# Wall_Clock.net
KiCad netlist of a schematic drawn in Altium Designer
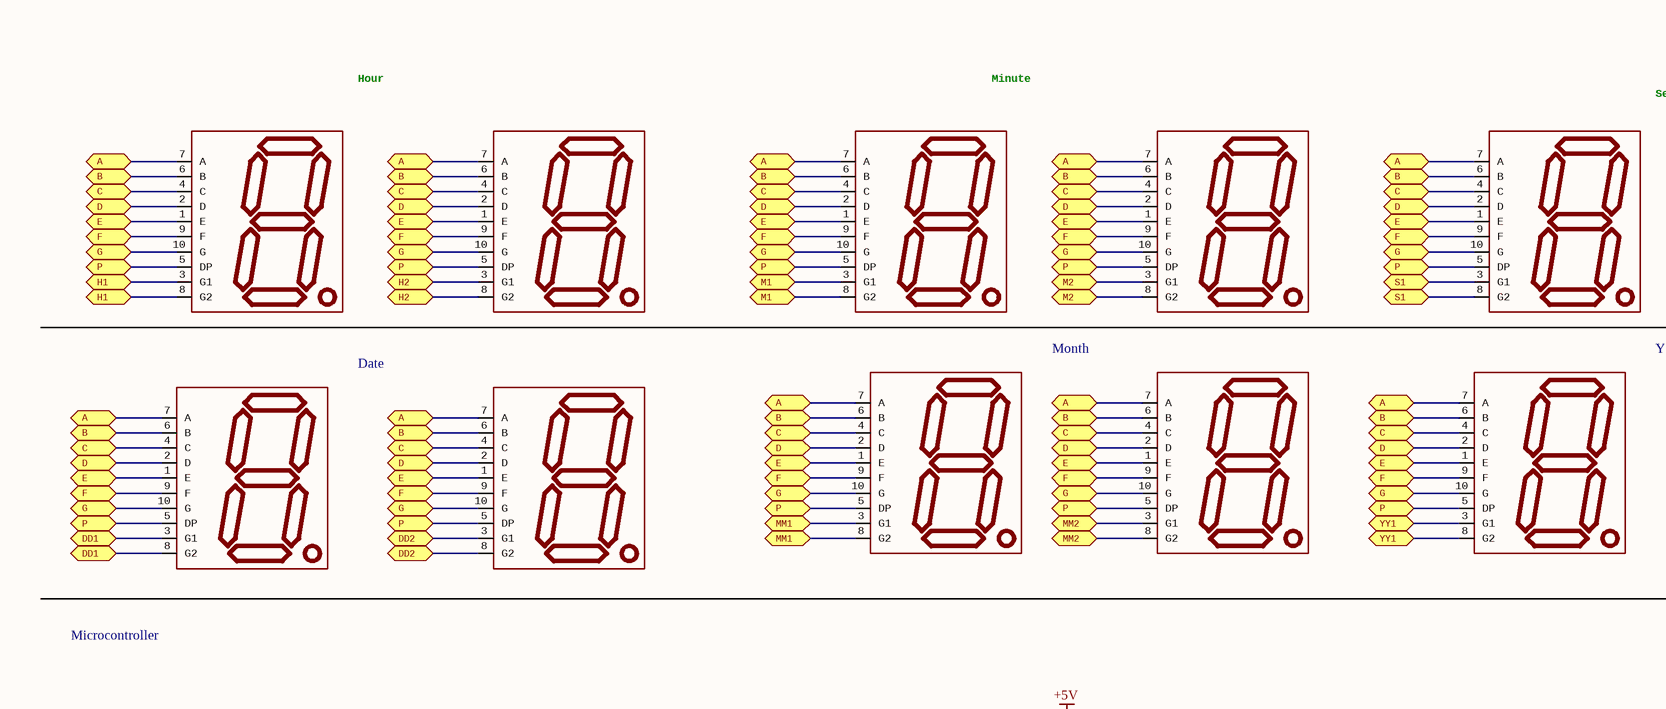
[diagram p0: Wall_Clock.SchDoc, top left]
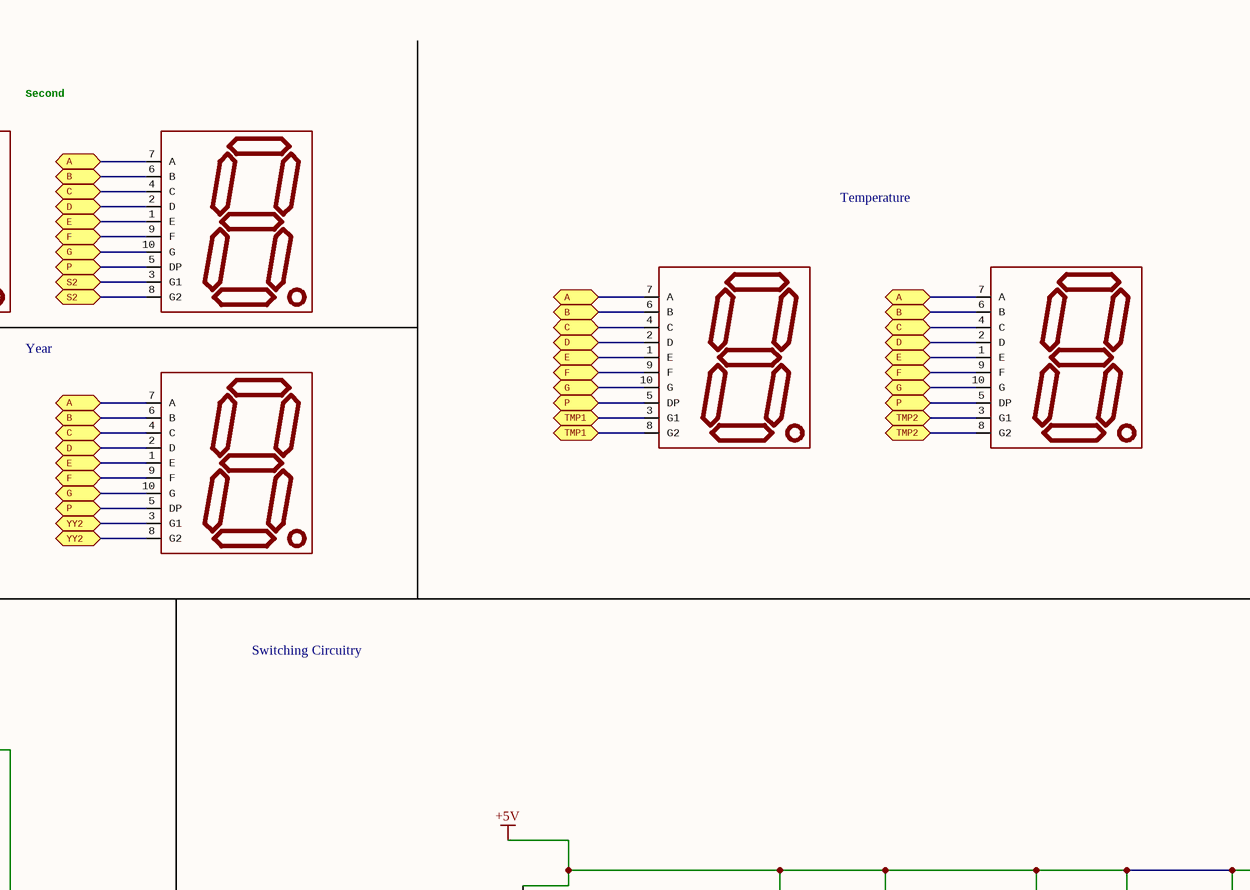
[diagram p1: Wall_Clock.SchDoc, top right]
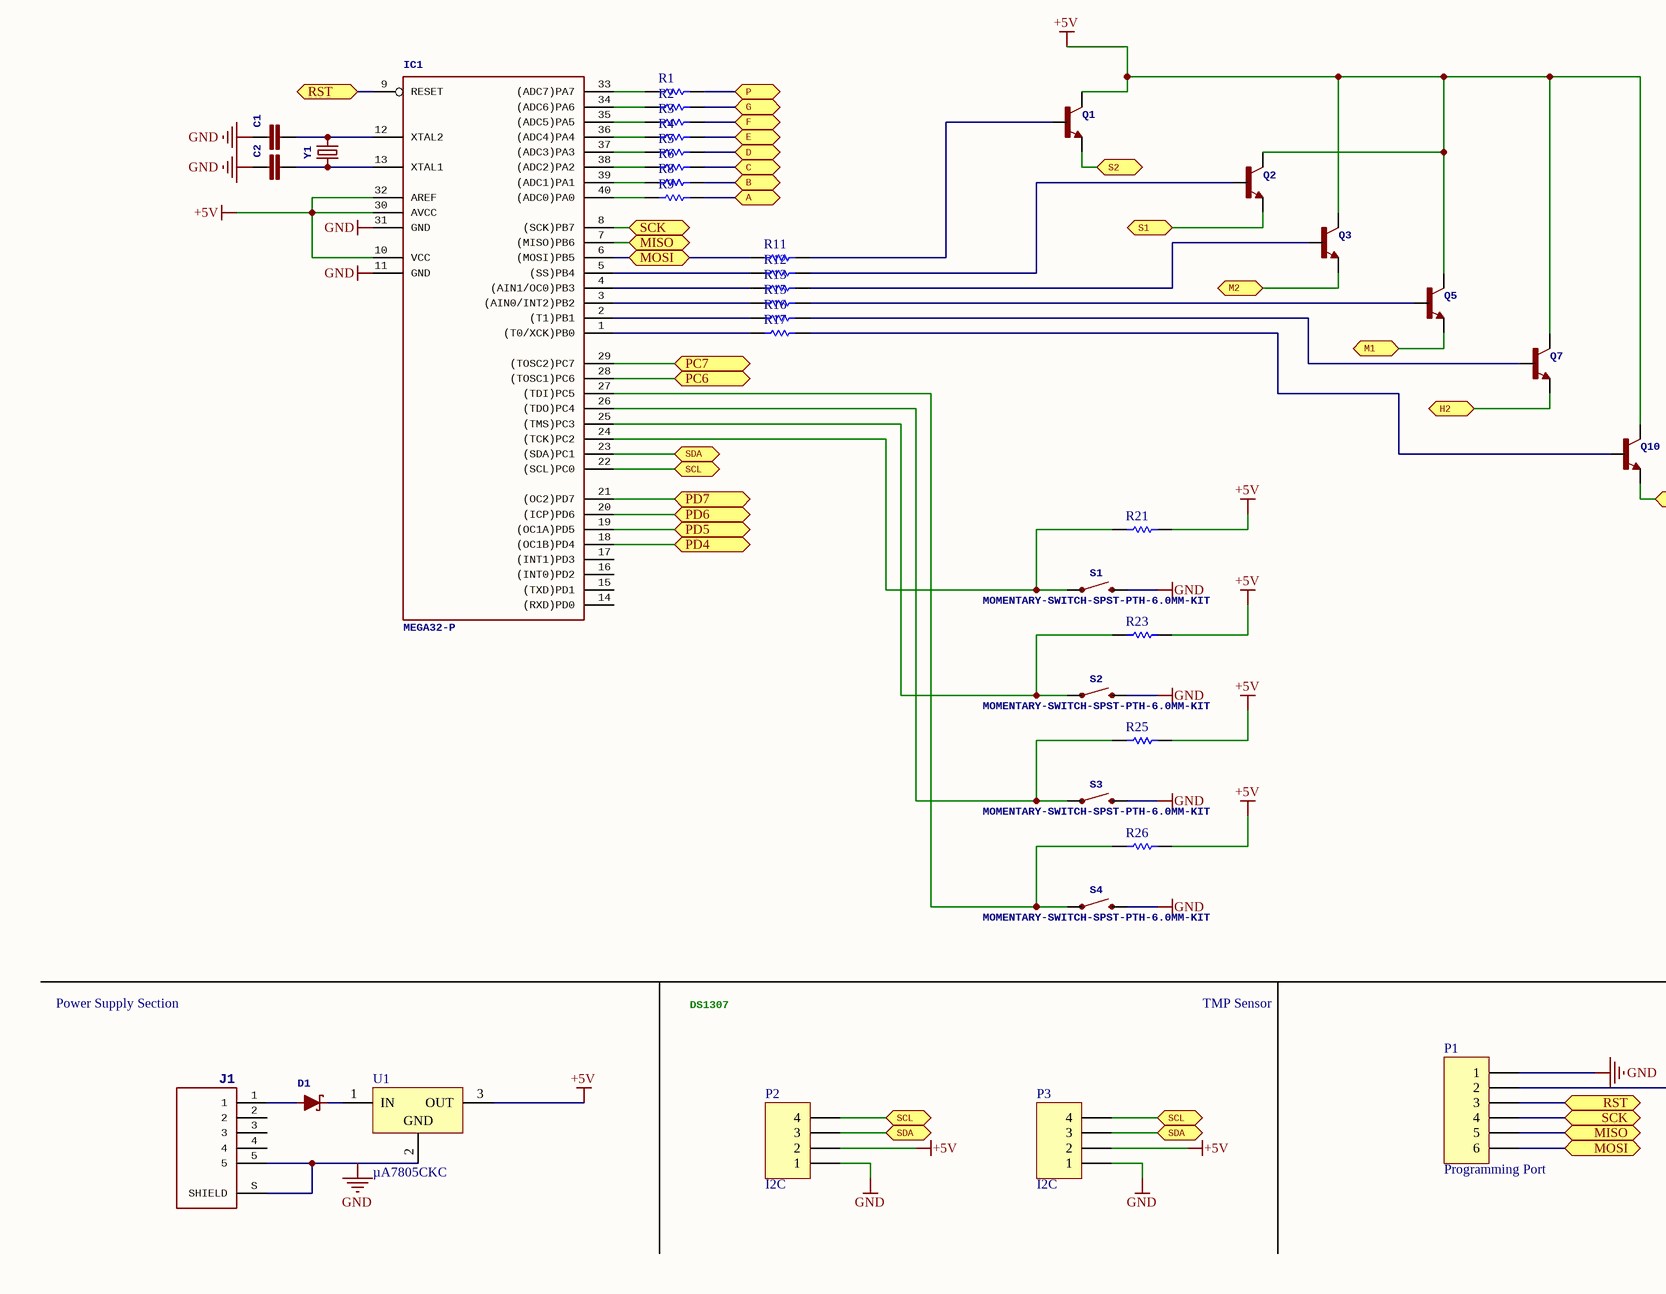
[diagram p2: Wall_Clock.SchDoc, bottom left]
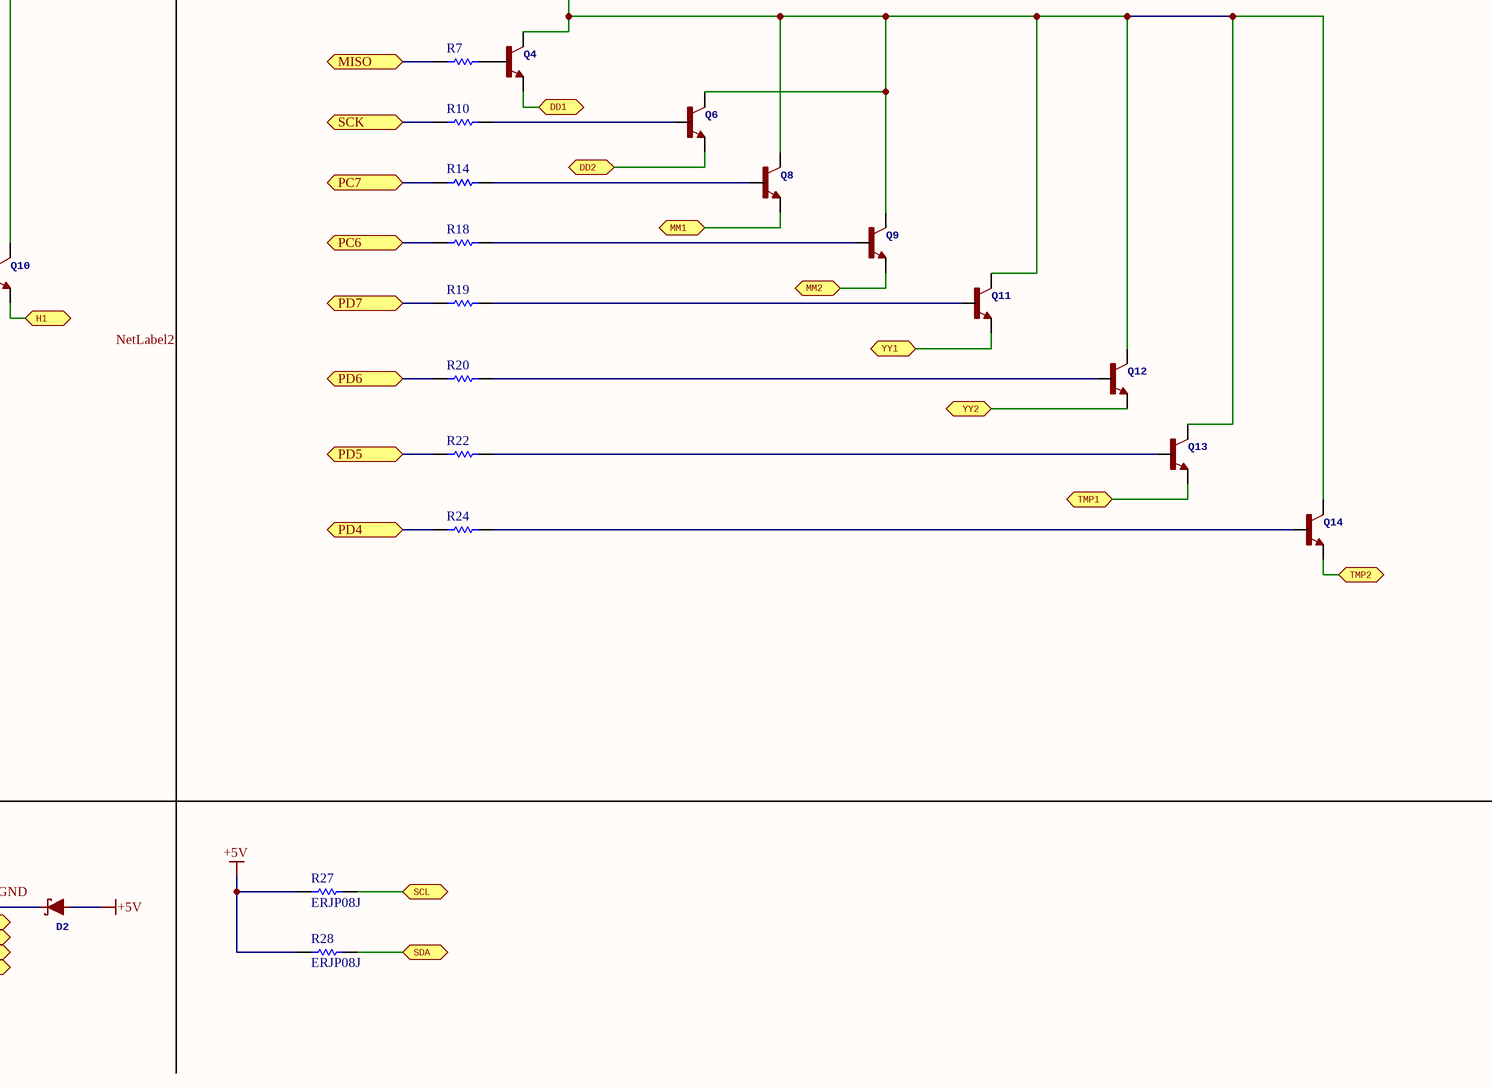
[diagram p3: Wall_Clock.SchDoc, bottom right]

(export (version "E")
  (design (tool "Eeschema 10.0.6"))
  (components
    (comp (ref "1")
      (value "7-SEGMENT-DISPLAYPTH")
      (footprint "7-SEGMENT-DISPLAY")
      (libsource (lib "SparkFun-Retired") (part "7-SEGMENT-DISPLAYPTH"))
    )
    (comp (ref "2")
      (value "7-SEGMENT-DISPLAYPTH")
      (footprint "7-SEGMENT-DISPLAY")
      (libsource (lib "SparkFun-Retired") (part "7-SEGMENT-DISPLAYPTH"))
    )
    (comp (ref "3")
      (value "7-SEGMENT-DISPLAYPTH")
      (footprint "7-SEGMENT-DISPLAY")
      (libsource (lib "SparkFun-Retired") (part "7-SEGMENT-DISPLAYPTH"))
    )
    (comp (ref "4")
      (value "7-SEGMENT-DISPLAYPTH")
      (footprint "7-SEGMENT-DISPLAY")
      (libsource (lib "SparkFun-Retired") (part "7-SEGMENT-DISPLAYPTH"))
    )
    (comp (ref "5")
      (value "7-SEGMENT-DISPLAYPTH")
      (footprint "7-SEGMENT-DISPLAY")
      (libsource (lib "SparkFun-Retired") (part "7-SEGMENT-DISPLAYPTH"))
    )
    (comp (ref "6")
      (value "7-SEGMENT-DISPLAYPTH")
      (footprint "7-SEGMENT-DISPLAY")
      (libsource (lib "SparkFun-Retired") (part "7-SEGMENT-DISPLAYPTH"))
    )
    (comp (ref "7")
      (value "7-SEGMENT-DISPLAYPTH")
      (footprint "7-SEGMENT-DISPLAY")
      (libsource (lib "SparkFun-Retired") (part "7-SEGMENT-DISPLAYPTH"))
    )
    (comp (ref "8")
      (value "7-SEGMENT-DISPLAYPTH")
      (footprint "7-SEGMENT-DISPLAY")
      (libsource (lib "SparkFun-Retired") (part "7-SEGMENT-DISPLAYPTH"))
    )
    (comp (ref "9")
      (value "7-SEGMENT-DISPLAYPTH")
      (footprint "7-SEGMENT-DISPLAY")
      (libsource (lib "SparkFun-Retired") (part "7-SEGMENT-DISPLAYPTH"))
    )
    (comp (ref "10")
      (value "7-SEGMENT-DISPLAYPTH")
      (footprint "7-SEGMENT-DISPLAY")
      (libsource (lib "SparkFun-Retired") (part "7-SEGMENT-DISPLAYPTH"))
    )
    (comp (ref "11")
      (value "7-SEGMENT-DISPLAYPTH")
      (footprint "7-SEGMENT-DISPLAY")
      (libsource (lib "SparkFun-Retired") (part "7-SEGMENT-DISPLAYPTH"))
    )
    (comp (ref "12")
      (value "7-SEGMENT-DISPLAYPTH")
      (footprint "7-SEGMENT-DISPLAY")
      (libsource (lib "SparkFun-Retired") (part "7-SEGMENT-DISPLAYPTH"))
    )
    (comp (ref "13")
      (value "7-SEGMENT-DISPLAYPTH")
      (footprint "7-SEGMENT-DISPLAY")
      (libsource (lib "SparkFun-Retired") (part "7-SEGMENT-DISPLAYPTH"))
    )
    (comp (ref "14")
      (value "7-SEGMENT-DISPLAYPTH")
      (footprint "7-SEGMENT-DISPLAY")
      (libsource (lib "SparkFun-Retired") (part "7-SEGMENT-DISPLAYPTH"))
    )
    (comp (ref "C1")
      (value "22PF-PTH-2.54MM-200V-5%")
      (footprint "CAP-PTH-2.54")
      (libsource (lib "SparkFun-Capacitors") (part "22PF-PTH-2.54MM-200V-5%"))
    )
    (comp (ref "C2")
      (value "22PF-PTH-2.54MM-200V-5%")
      (footprint "CAP-PTH-2.54")
      (libsource (lib "SparkFun-Capacitors") (part "22PF-PTH-2.54MM-200V-5%"))
    )
    (comp (ref "D1")
      (value "Schottky diode    A Schottky diode is a semiconductor diode which has a low forward voltage drop and a very fast switching action.")
      (footprint "SMA-DIODE")
      (libsource (lib "SparkFun-DiscreteSemi") (part "DIODE-SCHOTTKY-SS14"))
    )
    (comp (ref "D2")
      (value "Schottky diode    A Schottky diode is a semiconductor diode which has a low forward voltage drop and a very fast switching action.")
      (footprint "SMA-DIODE")
      (libsource (lib "SparkFun-DiscreteSemi") (part "DIODE-SCHOTTKY-SS14"))
    )
    (comp (ref "IC1")
      (value "MEGA32-P")
      (footprint "40P6")
      (fields (field (name "MPN") "ATMEGA32-16PU"))
      (libsource (lib "atmel") (part "MEGA32-P"))
    )
    (comp (ref "J1")
      (value "SMD+DIP Micro USB; MICRO-B-SMD")
      (footprint "HRS_ZX62D-B-5P8")
      (fields (field (name "MP") "ZX62D-B-5P8") (field (name "MF") "Hirose"))
      (libsource (lib "MicroUSB") (part "ZX62D-B-5P8"))
    )
    (comp (ref "P1")
      (value "Programming Port")
      (footprint "HDR1X6")
      (description "Header, 6-Pin")
      (fields (field (name "PUBLISHER") "Altium Limited"))
      (libsource (lib "Miscellaneous Connectors") (part "Header 6"))
    )
    (comp (ref "P2")
      (value "I2C")
      (footprint "HDR1X4")
      (description "Header, 4-Pin")
      (fields (field (name "PUBLISHER") "Altium Limited"))
      (libsource (lib "Miscellaneous Connectors") (part "Header 4"))
    )
    (comp (ref "P3")
      (value "I2C")
      (footprint "HDR1X4")
      (description "Header, 4-Pin")
      (fields (field (name "PUBLISHER") "Altium Limited"))
      (libsource (lib "Miscellaneous Connectors") (part "Header 4"))
    )
    (comp (ref "Q1")
      (value "NPN transistor    Current controlled devices typically used to amplify current or used as a switch.         BC547 -     COM-08928    (TO-92 45V 100mA) (1.Collector 2.Base 3.Emitter)             2N3904 -     COM-00521    (TO-92 40V 200mA) (1.Emitter 2.Base 3.Collector)             P2N2222A -     COM-12852    (TO-92 40V 600mA) (1.Collector 2.Base 3.Emitter)")
      (footprint "SOT23-3")
      (libsource (lib "SparkFun-DiscreteSemi") (part "TRANS_NPN-MMBT2222AL"))
    )
    (comp (ref "Q2")
      (value "NPN transistor    Current controlled devices typically used to amplify current or used as a switch.         BC547 -     COM-08928    (TO-92 45V 100mA) (1.Collector 2.Base 3.Emitter)             2N3904 -     COM-00521    (TO-92 40V 200mA) (1.Emitter 2.Base 3.Collector)             P2N2222A -     COM-12852    (TO-92 40V 600mA) (1.Collector 2.Base 3.Emitter)")
      (footprint "SOT23-3")
      (libsource (lib "SparkFun-DiscreteSemi") (part "TRANS_NPN-MMBT2222AL"))
    )
    (comp (ref "Q3")
      (value "NPN transistor    Current controlled devices typically used to amplify current or used as a switch.         BC547 -     COM-08928    (TO-92 45V 100mA) (1.Collector 2.Base 3.Emitter)             2N3904 -     COM-00521    (TO-92 40V 200mA) (1.Emitter 2.Base 3.Collector)             P2N2222A -     COM-12852    (TO-92 40V 600mA) (1.Collector 2.Base 3.Emitter)")
      (footprint "SOT23-3")
      (libsource (lib "SparkFun-DiscreteSemi") (part "TRANS_NPN-MMBT2222AL"))
    )
    (comp (ref "Q4")
      (value "NPN transistor    Current controlled devices typically used to amplify current or used as a switch.         BC547 -     COM-08928    (TO-92 45V 100mA) (1.Collector 2.Base 3.Emitter)             2N3904 -     COM-00521    (TO-92 40V 200mA) (1.Emitter 2.Base 3.Collector)             P2N2222A -     COM-12852    (TO-92 40V 600mA) (1.Collector 2.Base 3.Emitter)")
      (footprint "SOT23-3")
      (libsource (lib "SparkFun-DiscreteSemi") (part "TRANS_NPN-MMBT2222AL"))
    )
    (comp (ref "Q5")
      (value "NPN transistor    Current controlled devices typically used to amplify current or used as a switch.         BC547 -     COM-08928    (TO-92 45V 100mA) (1.Collector 2.Base 3.Emitter)             2N3904 -     COM-00521    (TO-92 40V 200mA) (1.Emitter 2.Base 3.Collector)             P2N2222A -     COM-12852    (TO-92 40V 600mA) (1.Collector 2.Base 3.Emitter)")
      (footprint "SOT23-3")
      (libsource (lib "SparkFun-DiscreteSemi") (part "TRANS_NPN-MMBT2222AL"))
    )
    (comp (ref "Q6")
      (value "NPN transistor    Current controlled devices typically used to amplify current or used as a switch.         BC547 -     COM-08928    (TO-92 45V 100mA) (1.Collector 2.Base 3.Emitter)             2N3904 -     COM-00521    (TO-92 40V 200mA) (1.Emitter 2.Base 3.Collector)             P2N2222A -     COM-12852    (TO-92 40V 600mA) (1.Collector 2.Base 3.Emitter)")
      (footprint "SOT23-3")
      (libsource (lib "SparkFun-DiscreteSemi") (part "TRANS_NPN-MMBT2222AL"))
    )
    (comp (ref "Q7")
      (value "NPN transistor    Current controlled devices typically used to amplify current or used as a switch.         BC547 -     COM-08928    (TO-92 45V 100mA) (1.Collector 2.Base 3.Emitter)             2N3904 -     COM-00521    (TO-92 40V 200mA) (1.Emitter 2.Base 3.Collector)             P2N2222A -     COM-12852    (TO-92 40V 600mA) (1.Collector 2.Base 3.Emitter)")
      (footprint "SOT23-3")
      (libsource (lib "SparkFun-DiscreteSemi") (part "TRANS_NPN-MMBT2222AL"))
    )
    (comp (ref "Q8")
      (value "NPN transistor    Current controlled devices typically used to amplify current or used as a switch.         BC547 -     COM-08928    (TO-92 45V 100mA) (1.Collector 2.Base 3.Emitter)             2N3904 -     COM-00521    (TO-92 40V 200mA) (1.Emitter 2.Base 3.Collector)             P2N2222A -     COM-12852    (TO-92 40V 600mA) (1.Collector 2.Base 3.Emitter)")
      (footprint "SOT23-3")
      (libsource (lib "SparkFun-DiscreteSemi") (part "TRANS_NPN-MMBT2222AL"))
    )
    (comp (ref "Q9")
      (value "NPN transistor    Current controlled devices typically used to amplify current or used as a switch.         BC547 -     COM-08928    (TO-92 45V 100mA) (1.Collector 2.Base 3.Emitter)             2N3904 -     COM-00521    (TO-92 40V 200mA) (1.Emitter 2.Base 3.Collector)             P2N2222A -     COM-12852    (TO-92 40V 600mA) (1.Collector 2.Base 3.Emitter)")
      (footprint "SOT23-3")
      (libsource (lib "SparkFun-DiscreteSemi") (part "TRANS_NPN-MMBT2222AL"))
    )
    (comp (ref "Q10")
      (value "NPN transistor    Current controlled devices typically used to amplify current or used as a switch.         BC547 -     COM-08928    (TO-92 45V 100mA) (1.Collector 2.Base 3.Emitter)             2N3904 -     COM-00521    (TO-92 40V 200mA) (1.Emitter 2.Base 3.Collector)             P2N2222A -     COM-12852    (TO-92 40V 600mA) (1.Collector 2.Base 3.Emitter)")
      (footprint "SOT23-3")
      (libsource (lib "SparkFun-DiscreteSemi") (part "TRANS_NPN-MMBT2222AL"))
    )
    (comp (ref "Q11")
      (value "NPN transistor    Current controlled devices typically used to amplify current or used as a switch.         BC547 -     COM-08928    (TO-92 45V 100mA) (1.Collector 2.Base 3.Emitter)             2N3904 -     COM-00521    (TO-92 40V 200mA) (1.Emitter 2.Base 3.Collector)             P2N2222A -     COM-12852    (TO-92 40V 600mA) (1.Collector 2.Base 3.Emitter)")
      (footprint "SOT23-3")
      (libsource (lib "SparkFun-DiscreteSemi") (part "TRANS_NPN-MMBT2222AL"))
    )
    (comp (ref "Q12")
      (value "NPN transistor    Current controlled devices typically used to amplify current or used as a switch.         BC547 -     COM-08928    (TO-92 45V 100mA) (1.Collector 2.Base 3.Emitter)             2N3904 -     COM-00521    (TO-92 40V 200mA) (1.Emitter 2.Base 3.Collector)             P2N2222A -     COM-12852    (TO-92 40V 600mA) (1.Collector 2.Base 3.Emitter)")
      (footprint "SOT23-3")
      (libsource (lib "SparkFun-DiscreteSemi") (part "TRANS_NPN-MMBT2222AL"))
    )
    (comp (ref "Q13")
      (value "NPN transistor    Current controlled devices typically used to amplify current or used as a switch.         BC547 -     COM-08928    (TO-92 45V 100mA) (1.Collector 2.Base 3.Emitter)             2N3904 -     COM-00521    (TO-92 40V 200mA) (1.Emitter 2.Base 3.Collector)             P2N2222A -     COM-12852    (TO-92 40V 600mA) (1.Collector 2.Base 3.Emitter)")
      (footprint "SOT23-3")
      (libsource (lib "SparkFun-DiscreteSemi") (part "TRANS_NPN-MMBT2222AL"))
    )
    (comp (ref "Q14")
      (value "NPN transistor    Current controlled devices typically used to amplify current or used as a switch.         BC547 -     COM-08928    (TO-92 45V 100mA) (1.Collector 2.Base 3.Emitter)             2N3904 -     COM-00521    (TO-92 40V 200mA) (1.Emitter 2.Base 3.Collector)             P2N2222A -     COM-12852    (TO-92 40V 600mA) (1.Collector 2.Base 3.Emitter)")
      (footprint "SOT23-3")
      (libsource (lib "SparkFun-DiscreteSemi") (part "TRANS_NPN-MMBT2222AL"))
    )
    (comp (ref "R1")
      (value "~")
      (footprint "8-1206")
      (description "Anti-Surge Thick Film Chip Resistor, 10 Ohm to 1M Ohm Range, 5% Tolerance, 1206 Size, 0.25 W")
      (fields (field (name "PUBLISHER") "Altium Limited"))
      (libsource (lib "Panasonic Resistor") (part "ERJP08J"))
    )
    (comp (ref "R2")
      (value "~")
      (footprint "8-1206")
      (description "Anti-Surge Thick Film Chip Resistor, 10 Ohm to 1M Ohm Range, 5% Tolerance, 1206 Size, 0.25 W")
      (fields (field (name "PUBLISHER") "Altium Limited"))
      (libsource (lib "Panasonic Resistor") (part "ERJP08J"))
    )
    (comp (ref "R3")
      (value "~")
      (footprint "8-1206")
      (description "Anti-Surge Thick Film Chip Resistor, 10 Ohm to 1M Ohm Range, 5% Tolerance, 1206 Size, 0.25 W")
      (fields (field (name "PUBLISHER") "Altium Limited"))
      (libsource (lib "Panasonic Resistor") (part "ERJP08J"))
    )
    (comp (ref "R4")
      (value "~")
      (footprint "8-1206")
      (description "Anti-Surge Thick Film Chip Resistor, 10 Ohm to 1M Ohm Range, 5% Tolerance, 1206 Size, 0.25 W")
      (fields (field (name "PUBLISHER") "Altium Limited"))
      (libsource (lib "Panasonic Resistor") (part "ERJP08J"))
    )
    (comp (ref "R5")
      (value "~")
      (footprint "8-1206")
      (description "Anti-Surge Thick Film Chip Resistor, 10 Ohm to 1M Ohm Range, 5% Tolerance, 1206 Size, 0.25 W")
      (fields (field (name "PUBLISHER") "Altium Limited"))
      (libsource (lib "Panasonic Resistor") (part "ERJP08J"))
    )
    (comp (ref "R6")
      (value "~")
      (footprint "8-1206")
      (description "Anti-Surge Thick Film Chip Resistor, 10 Ohm to 1M Ohm Range, 5% Tolerance, 1206 Size, 0.25 W")
      (fields (field (name "PUBLISHER") "Altium Limited"))
      (libsource (lib "Panasonic Resistor") (part "ERJP08J"))
    )
    (comp (ref "R7")
      (value "~")
      (footprint "8-1206")
      (description "Anti-Surge Thick Film Chip Resistor, 10 Ohm to 1M Ohm Range, 5% Tolerance, 1206 Size, 0.25 W")
      (fields (field (name "PUBLISHER") "Altium Limited"))
      (libsource (lib "Panasonic Resistor") (part "ERJP08J"))
    )
    (comp (ref "R8")
      (value "~")
      (footprint "8-1206")
      (description "Anti-Surge Thick Film Chip Resistor, 10 Ohm to 1M Ohm Range, 5% Tolerance, 1206 Size, 0.25 W")
      (fields (field (name "PUBLISHER") "Altium Limited"))
      (libsource (lib "Panasonic Resistor") (part "ERJP08J"))
    )
    (comp (ref "R9")
      (value "~")
      (footprint "8-1206")
      (description "Anti-Surge Thick Film Chip Resistor, 10 Ohm to 1M Ohm Range, 5% Tolerance, 1206 Size, 0.25 W")
      (fields (field (name "PUBLISHER") "Altium Limited"))
      (libsource (lib "Panasonic Resistor") (part "ERJP08J"))
    )
    (comp (ref "R10")
      (value "~")
      (footprint "8-1206")
      (description "Anti-Surge Thick Film Chip Resistor, 10 Ohm to 1M Ohm Range, 5% Tolerance, 1206 Size, 0.25 W")
      (fields (field (name "PUBLISHER") "Altium Limited"))
      (libsource (lib "Panasonic Resistor") (part "ERJP08J"))
    )
    (comp (ref "R11")
      (value "~")
      (footprint "8-1206")
      (description "Anti-Surge Thick Film Chip Resistor, 10 Ohm to 1M Ohm Range, 5% Tolerance, 1206 Size, 0.25 W")
      (fields (field (name "PUBLISHER") "Altium Limited"))
      (libsource (lib "Panasonic Resistor") (part "ERJP08J"))
    )
    (comp (ref "R12")
      (value "~")
      (footprint "8-1206")
      (description "Anti-Surge Thick Film Chip Resistor, 10 Ohm to 1M Ohm Range, 5% Tolerance, 1206 Size, 0.25 W")
      (fields (field (name "PUBLISHER") "Altium Limited"))
      (libsource (lib "Panasonic Resistor") (part "ERJP08J"))
    )
    (comp (ref "R13")
      (value "~")
      (footprint "8-1206")
      (description "Anti-Surge Thick Film Chip Resistor, 10 Ohm to 1M Ohm Range, 5% Tolerance, 1206 Size, 0.25 W")
      (fields (field (name "PUBLISHER") "Altium Limited"))
      (libsource (lib "Panasonic Resistor") (part "ERJP08J"))
    )
    (comp (ref "R14")
      (value "~")
      (footprint "8-1206")
      (description "Anti-Surge Thick Film Chip Resistor, 10 Ohm to 1M Ohm Range, 5% Tolerance, 1206 Size, 0.25 W")
      (fields (field (name "PUBLISHER") "Altium Limited"))
      (libsource (lib "Panasonic Resistor") (part "ERJP08J"))
    )
    (comp (ref "R15")
      (value "~")
      (footprint "8-1206")
      (description "Anti-Surge Thick Film Chip Resistor, 10 Ohm to 1M Ohm Range, 5% Tolerance, 1206 Size, 0.25 W")
      (fields (field (name "PUBLISHER") "Altium Limited"))
      (libsource (lib "Panasonic Resistor") (part "ERJP08J"))
    )
    (comp (ref "R16")
      (value "~")
      (footprint "8-1206")
      (description "Anti-Surge Thick Film Chip Resistor, 10 Ohm to 1M Ohm Range, 5% Tolerance, 1206 Size, 0.25 W")
      (fields (field (name "PUBLISHER") "Altium Limited"))
      (libsource (lib "Panasonic Resistor") (part "ERJP08J"))
    )
    (comp (ref "R17")
      (value "~")
      (footprint "8-1206")
      (description "Anti-Surge Thick Film Chip Resistor, 10 Ohm to 1M Ohm Range, 5% Tolerance, 1206 Size, 0.25 W")
      (fields (field (name "PUBLISHER") "Altium Limited"))
      (libsource (lib "Panasonic Resistor") (part "ERJP08J"))
    )
    (comp (ref "R18")
      (value "~")
      (footprint "8-1206")
      (description "Anti-Surge Thick Film Chip Resistor, 10 Ohm to 1M Ohm Range, 5% Tolerance, 1206 Size, 0.25 W")
      (fields (field (name "PUBLISHER") "Altium Limited"))
      (libsource (lib "Panasonic Resistor") (part "ERJP08J"))
    )
    (comp (ref "R19")
      (value "~")
      (footprint "8-1206")
      (description "Anti-Surge Thick Film Chip Resistor, 10 Ohm to 1M Ohm Range, 5% Tolerance, 1206 Size, 0.25 W")
      (fields (field (name "PUBLISHER") "Altium Limited"))
      (libsource (lib "Panasonic Resistor") (part "ERJP08J"))
    )
    (comp (ref "R20")
      (value "~")
      (footprint "8-1206")
      (description "Anti-Surge Thick Film Chip Resistor, 10 Ohm to 1M Ohm Range, 5% Tolerance, 1206 Size, 0.25 W")
      (fields (field (name "PUBLISHER") "Altium Limited"))
      (libsource (lib "Panasonic Resistor") (part "ERJP08J"))
    )
    (comp (ref "R21")
      (value "~")
      (footprint "8-1206")
      (description "Anti-Surge Thick Film Chip Resistor, 10 Ohm to 1M Ohm Range, 5% Tolerance, 1206 Size, 0.25 W")
      (fields (field (name "PUBLISHER") "Altium Limited"))
      (libsource (lib "Panasonic Resistor") (part "ERJP08J"))
    )
    (comp (ref "R22")
      (value "~")
      (footprint "8-1206")
      (description "Anti-Surge Thick Film Chip Resistor, 10 Ohm to 1M Ohm Range, 5% Tolerance, 1206 Size, 0.25 W")
      (fields (field (name "PUBLISHER") "Altium Limited"))
      (libsource (lib "Panasonic Resistor") (part "ERJP08J"))
    )
    (comp (ref "R23")
      (value "~")
      (footprint "8-1206")
      (description "Anti-Surge Thick Film Chip Resistor, 10 Ohm to 1M Ohm Range, 5% Tolerance, 1206 Size, 0.25 W")
      (fields (field (name "PUBLISHER") "Altium Limited"))
      (libsource (lib "Panasonic Resistor") (part "ERJP08J"))
    )
    (comp (ref "R24")
      (value "~")
      (footprint "8-1206")
      (description "Anti-Surge Thick Film Chip Resistor, 10 Ohm to 1M Ohm Range, 5% Tolerance, 1206 Size, 0.25 W")
      (fields (field (name "PUBLISHER") "Altium Limited"))
      (libsource (lib "Panasonic Resistor") (part "ERJP08J"))
    )
    (comp (ref "R25")
      (value "~")
      (footprint "8-1206")
      (description "Anti-Surge Thick Film Chip Resistor, 10 Ohm to 1M Ohm Range, 5% Tolerance, 1206 Size, 0.25 W")
      (fields (field (name "PUBLISHER") "Altium Limited"))
      (libsource (lib "Panasonic Resistor") (part "ERJP08J"))
    )
    (comp (ref "R26")
      (value "~")
      (footprint "8-1206")
      (description "Anti-Surge Thick Film Chip Resistor, 10 Ohm to 1M Ohm Range, 5% Tolerance, 1206 Size, 0.25 W")
      (fields (field (name "PUBLISHER") "Altium Limited"))
      (libsource (lib "Panasonic Resistor") (part "ERJP08J"))
    )
    (comp (ref "R27")
      (value "ERJP08J")
      (footprint "8-1206")
      (description "Anti-Surge Thick Film Chip Resistor, 10 Ohm to 1M Ohm Range, 5% Tolerance, 1206 Size, 0.25 W")
      (fields (field (name "PUBLISHER") "Altium Limited"))
      (libsource (lib "Panasonic Resistor") (part "ERJP08J"))
    )
    (comp (ref "R28")
      (value "ERJP08J")
      (footprint "8-1206")
      (description "Anti-Surge Thick Film Chip Resistor, 10 Ohm to 1M Ohm Range, 5% Tolerance, 1206 Size, 0.25 W")
      (fields (field (name "PUBLISHER") "Altium Limited"))
      (libsource (lib "Panasonic Resistor") (part "ERJP08J"))
    )
    (comp (ref "S1")
      (value "MOMENTARY-SWITCH-SPST-PTH-6.0MM-KIT")
      (footprint "TACTILE_SWITCH_PTH_6.0MM_KIT")
      (libsource (lib "SparkFun-Switches") (part "MOMENTARY-SWITCH-SPST-PTH-6.0MM-KIT"))
    )
    (comp (ref "S2")
      (value "MOMENTARY-SWITCH-SPST-PTH-6.0MM-KIT")
      (footprint "TACTILE_SWITCH_PTH_6.0MM_KIT")
      (libsource (lib "SparkFun-Switches") (part "MOMENTARY-SWITCH-SPST-PTH-6.0MM-KIT"))
    )
    (comp (ref "S3")
      (value "MOMENTARY-SWITCH-SPST-PTH-6.0MM-KIT")
      (footprint "TACTILE_SWITCH_PTH_6.0MM_KIT")
      (libsource (lib "SparkFun-Switches") (part "MOMENTARY-SWITCH-SPST-PTH-6.0MM-KIT"))
    )
    (comp (ref "S4")
      (value "MOMENTARY-SWITCH-SPST-PTH-6.0MM-KIT")
      (footprint "TACTILE_SWITCH_PTH_6.0MM_KIT")
      (libsource (lib "SparkFun-Switches") (part "MOMENTARY-SWITCH-SPST-PTH-6.0MM-KIT"))
    )
    (comp (ref "U1")
      (value "µA7805CKC")
      (footprint "KC03")
      (description "Positive-Voltage Regulator")
      (fields (field (name "PUBLISHER") "Altium Limited"))
      (libsource (lib "TI Power Mgt Voltage Regulator") (part "µA7805CKC"))
    )
    (comp (ref "Y1")
      (value "CRYSTAL-16MHZPTH-HC49US")
      (footprint "HC49US")
      (libsource (lib "SparkFun-Clocks") (part "CRYSTAL-16MHZPTH-HC49US"))
    )
  )
  (nets
    (net (code "1") (name "+5V") (class "Default")
      (node (ref "D2") (pin "A") (pinfunction "A_A") (pintype "passive"))
      (node (ref "IC1") (pin "10") (pinfunction "VCC_10") (pintype "power_in"))
      (node (ref "IC1") (pin "30") (pinfunction "AVCC_30") (pintype "power_in"))
      (node (ref "IC1") (pin "32") (pinfunction "AREF_32") (pintype "passive"))
      (node (ref "P2") (pin "2") (pinfunction "2_2") (pintype "passive"))
      (node (ref "P3") (pin "2") (pinfunction "2_2") (pintype "passive"))
      (node (ref "Q1") (pin "3") (pinfunction "C_3") (pintype "passive"))
      (node (ref "Q10") (pin "3") (pinfunction "C_3") (pintype "passive"))
      (node (ref "Q11") (pin "3") (pinfunction "C_3") (pintype "passive"))
      (node (ref "Q12") (pin "3") (pinfunction "C_3") (pintype "passive"))
      (node (ref "Q13") (pin "3") (pinfunction "C_3") (pintype "passive"))
      (node (ref "Q14") (pin "3") (pinfunction "C_3") (pintype "passive"))
      (node (ref "Q2") (pin "3") (pinfunction "C_3") (pintype "passive"))
      (node (ref "Q3") (pin "3") (pinfunction "C_3") (pintype "passive"))
      (node (ref "Q4") (pin "3") (pinfunction "C_3") (pintype "passive"))
      (node (ref "Q5") (pin "3") (pinfunction "C_3") (pintype "passive"))
      (node (ref "Q6") (pin "3") (pinfunction "C_3") (pintype "passive"))
      (node (ref "Q7") (pin "3") (pinfunction "C_3") (pintype "passive"))
      (node (ref "Q8") (pin "3") (pinfunction "C_3") (pintype "passive"))
      (node (ref "Q9") (pin "3") (pinfunction "C_3") (pintype "passive"))
      (node (ref "R21") (pin "2") (pinfunction "2_2") (pintype "passive"))
      (node (ref "R23") (pin "2") (pinfunction "2_2") (pintype "passive"))
      (node (ref "R25") (pin "2") (pinfunction "2_2") (pintype "passive"))
      (node (ref "R26") (pin "2") (pinfunction "2_2") (pintype "passive"))
      (node (ref "R27") (pin "1") (pinfunction "1_1") (pintype "passive"))
      (node (ref "R28") (pin "1") (pinfunction "1_1") (pintype "passive"))
      (node (ref "U1") (pin "3") (pinfunction "OUT_3") (pintype "power_in"))
    )
    (net (code "2") (name "/A") (class "Default")
      (node (ref "1") (pin "7") (pinfunction "A_7") (pintype "passive"))
      (node (ref "10") (pin "7") (pinfunction "A_7") (pintype "passive"))
      (node (ref "11") (pin "7") (pinfunction "A_7") (pintype "passive"))
      (node (ref "12") (pin "7") (pinfunction "A_7") (pintype "passive"))
      (node (ref "13") (pin "7") (pinfunction "A_7") (pintype "passive"))
      (node (ref "14") (pin "7") (pinfunction "A_7") (pintype "passive"))
      (node (ref "2") (pin "7") (pinfunction "A_7") (pintype "passive"))
      (node (ref "3") (pin "7") (pinfunction "A_7") (pintype "passive"))
      (node (ref "4") (pin "7") (pinfunction "A_7") (pintype "passive"))
      (node (ref "5") (pin "7") (pinfunction "A_7") (pintype "passive"))
      (node (ref "6") (pin "7") (pinfunction "A_7") (pintype "passive"))
      (node (ref "7") (pin "7") (pinfunction "A_7") (pintype "passive"))
      (node (ref "8") (pin "7") (pinfunction "A_7") (pintype "passive"))
      (node (ref "9") (pin "7") (pinfunction "A_7") (pintype "passive"))
      (node (ref "R9") (pin "2") (pinfunction "2_2") (pintype "passive"))
    )
    (net (code "3") (name "/B") (class "Default")
      (node (ref "1") (pin "6") (pinfunction "B_6") (pintype "passive"))
      (node (ref "10") (pin "6") (pinfunction "B_6") (pintype "passive"))
      (node (ref "11") (pin "6") (pinfunction "B_6") (pintype "passive"))
      (node (ref "12") (pin "6") (pinfunction "B_6") (pintype "passive"))
      (node (ref "13") (pin "6") (pinfunction "B_6") (pintype "passive"))
      (node (ref "14") (pin "6") (pinfunction "B_6") (pintype "passive"))
      (node (ref "2") (pin "6") (pinfunction "B_6") (pintype "passive"))
      (node (ref "3") (pin "6") (pinfunction "B_6") (pintype "passive"))
      (node (ref "4") (pin "6") (pinfunction "B_6") (pintype "passive"))
      (node (ref "5") (pin "6") (pinfunction "B_6") (pintype "passive"))
      (node (ref "6") (pin "6") (pinfunction "B_6") (pintype "passive"))
      (node (ref "7") (pin "6") (pinfunction "B_6") (pintype "passive"))
      (node (ref "8") (pin "6") (pinfunction "B_6") (pintype "passive"))
      (node (ref "9") (pin "6") (pinfunction "B_6") (pintype "passive"))
      (node (ref "R8") (pin "2") (pinfunction "2_2") (pintype "passive"))
    )
    (net (code "4") (name "/C") (class "Default")
      (node (ref "1") (pin "4") (pinfunction "C_4") (pintype "passive"))
      (node (ref "10") (pin "4") (pinfunction "C_4") (pintype "passive"))
      (node (ref "11") (pin "4") (pinfunction "C_4") (pintype "passive"))
      (node (ref "12") (pin "4") (pinfunction "C_4") (pintype "passive"))
      (node (ref "13") (pin "4") (pinfunction "C_4") (pintype "passive"))
      (node (ref "14") (pin "4") (pinfunction "C_4") (pintype "passive"))
      (node (ref "2") (pin "4") (pinfunction "C_4") (pintype "passive"))
      (node (ref "3") (pin "4") (pinfunction "C_4") (pintype "passive"))
      (node (ref "4") (pin "4") (pinfunction "C_4") (pintype "passive"))
      (node (ref "5") (pin "4") (pinfunction "C_4") (pintype "passive"))
      (node (ref "6") (pin "4") (pinfunction "C_4") (pintype "passive"))
      (node (ref "7") (pin "4") (pinfunction "C_4") (pintype "passive"))
      (node (ref "8") (pin "4") (pinfunction "C_4") (pintype "passive"))
      (node (ref "9") (pin "4") (pinfunction "C_4") (pintype "passive"))
      (node (ref "R6") (pin "2") (pinfunction "2_2") (pintype "passive"))
    )
    (net (code "5") (name "/D") (class "Default")
      (node (ref "1") (pin "2") (pinfunction "D_2") (pintype "passive"))
      (node (ref "10") (pin "2") (pinfunction "D_2") (pintype "passive"))
      (node (ref "11") (pin "2") (pinfunction "D_2") (pintype "passive"))
      (node (ref "12") (pin "2") (pinfunction "D_2") (pintype "passive"))
      (node (ref "13") (pin "2") (pinfunction "D_2") (pintype "passive"))
      (node (ref "14") (pin "2") (pinfunction "D_2") (pintype "passive"))
      (node (ref "2") (pin "2") (pinfunction "D_2") (pintype "passive"))
      (node (ref "3") (pin "2") (pinfunction "D_2") (pintype "passive"))
      (node (ref "4") (pin "2") (pinfunction "D_2") (pintype "passive"))
      (node (ref "5") (pin "2") (pinfunction "D_2") (pintype "passive"))
      (node (ref "6") (pin "2") (pinfunction "D_2") (pintype "passive"))
      (node (ref "7") (pin "2") (pinfunction "D_2") (pintype "passive"))
      (node (ref "8") (pin "2") (pinfunction "D_2") (pintype "passive"))
      (node (ref "9") (pin "2") (pinfunction "D_2") (pintype "passive"))
      (node (ref "R5") (pin "2") (pinfunction "2_2") (pintype "passive"))
    )
    (net (code "6") (name "/DD1") (class "Default")
      (node (ref "13") (pin "3") (pinfunction "G1_3") (pintype "passive"))
      (node (ref "13") (pin "8") (pinfunction "G2_8") (pintype "passive"))
      (node (ref "Q4") (pin "2") (pinfunction "E_2") (pintype "passive"))
    )
    (net (code "7") (name "/DD2") (class "Default")
      (node (ref "14") (pin "3") (pinfunction "G1_3") (pintype "passive"))
      (node (ref "14") (pin "8") (pinfunction "G2_8") (pintype "passive"))
      (node (ref "Q6") (pin "2") (pinfunction "E_2") (pintype "passive"))
    )
    (net (code "8") (name "/E") (class "Default")
      (node (ref "1") (pin "1") (pinfunction "E_1") (pintype "passive"))
      (node (ref "10") (pin "1") (pinfunction "E_1") (pintype "passive"))
      (node (ref "11") (pin "1") (pinfunction "E_1") (pintype "passive"))
      (node (ref "12") (pin "1") (pinfunction "E_1") (pintype "passive"))
      (node (ref "13") (pin "1") (pinfunction "E_1") (pintype "passive"))
      (node (ref "14") (pin "1") (pinfunction "E_1") (pintype "passive"))
      (node (ref "2") (pin "1") (pinfunction "E_1") (pintype "passive"))
      (node (ref "3") (pin "1") (pinfunction "E_1") (pintype "passive"))
      (node (ref "4") (pin "1") (pinfunction "E_1") (pintype "passive"))
      (node (ref "5") (pin "1") (pinfunction "E_1") (pintype "passive"))
      (node (ref "6") (pin "1") (pinfunction "E_1") (pintype "passive"))
      (node (ref "7") (pin "1") (pinfunction "E_1") (pintype "passive"))
      (node (ref "8") (pin "1") (pinfunction "E_1") (pintype "passive"))
      (node (ref "9") (pin "1") (pinfunction "E_1") (pintype "passive"))
      (node (ref "R4") (pin "2") (pinfunction "2_2") (pintype "passive"))
    )
    (net (code "9") (name "/F") (class "Default")
      (node (ref "1") (pin "9") (pinfunction "F_9") (pintype "passive"))
      (node (ref "10") (pin "9") (pinfunction "F_9") (pintype "passive"))
      (node (ref "11") (pin "9") (pinfunction "F_9") (pintype "passive"))
      (node (ref "12") (pin "9") (pinfunction "F_9") (pintype "passive"))
      (node (ref "13") (pin "9") (pinfunction "F_9") (pintype "passive"))
      (node (ref "14") (pin "9") (pinfunction "F_9") (pintype "passive"))
      (node (ref "2") (pin "9") (pinfunction "F_9") (pintype "passive"))
      (node (ref "3") (pin "9") (pinfunction "F_9") (pintype "passive"))
      (node (ref "4") (pin "9") (pinfunction "F_9") (pintype "passive"))
      (node (ref "5") (pin "9") (pinfunction "F_9") (pintype "passive"))
      (node (ref "6") (pin "9") (pinfunction "F_9") (pintype "passive"))
      (node (ref "7") (pin "9") (pinfunction "F_9") (pintype "passive"))
      (node (ref "8") (pin "9") (pinfunction "F_9") (pintype "passive"))
      (node (ref "9") (pin "9") (pinfunction "F_9") (pintype "passive"))
      (node (ref "R3") (pin "2") (pinfunction "2_2") (pintype "passive"))
    )
    (net (code "10") (name "/G") (class "Default")
      (node (ref "1") (pin "10") (pinfunction "G_10") (pintype "passive"))
      (node (ref "10") (pin "10") (pinfunction "G_10") (pintype "passive"))
      (node (ref "11") (pin "10") (pinfunction "G_10") (pintype "passive"))
      (node (ref "12") (pin "10") (pinfunction "G_10") (pintype "passive"))
      (node (ref "13") (pin "10") (pinfunction "G_10") (pintype "passive"))
      (node (ref "14") (pin "10") (pinfunction "G_10") (pintype "passive"))
      (node (ref "2") (pin "10") (pinfunction "G_10") (pintype "passive"))
      (node (ref "3") (pin "10") (pinfunction "G_10") (pintype "passive"))
      (node (ref "4") (pin "10") (pinfunction "G_10") (pintype "passive"))
      (node (ref "5") (pin "10") (pinfunction "G_10") (pintype "passive"))
      (node (ref "6") (pin "10") (pinfunction "G_10") (pintype "passive"))
      (node (ref "7") (pin "10") (pinfunction "G_10") (pintype "passive"))
      (node (ref "8") (pin "10") (pinfunction "G_10") (pintype "passive"))
      (node (ref "9") (pin "10") (pinfunction "G_10") (pintype "passive"))
      (node (ref "R2") (pin "2") (pinfunction "2_2") (pintype "passive"))
    )
    (net (code "11") (name "/H1") (class "Default")
      (node (ref "1") (pin "3") (pinfunction "G1_3") (pintype "passive"))
      (node (ref "1") (pin "8") (pinfunction "G2_8") (pintype "passive"))
      (node (ref "Q10") (pin "2") (pinfunction "E_2") (pintype "passive"))
    )
    (net (code "12") (name "/H2") (class "Default")
      (node (ref "2") (pin "3") (pinfunction "G1_3") (pintype "passive"))
      (node (ref "2") (pin "8") (pinfunction "G2_8") (pintype "passive"))
      (node (ref "Q7") (pin "2") (pinfunction "E_2") (pintype "passive"))
    )
    (net (code "13") (name "/M1") (class "Default")
      (node (ref "3") (pin "3") (pinfunction "G1_3") (pintype "passive"))
      (node (ref "3") (pin "8") (pinfunction "G2_8") (pintype "passive"))
      (node (ref "Q5") (pin "2") (pinfunction "E_2") (pintype "passive"))
    )
    (net (code "14") (name "/M2") (class "Default")
      (node (ref "4") (pin "3") (pinfunction "G1_3") (pintype "passive"))
      (node (ref "4") (pin "8") (pinfunction "G2_8") (pintype "passive"))
      (node (ref "Q3") (pin "2") (pinfunction "E_2") (pintype "passive"))
    )
    (net (code "15") (name "/MISO") (class "Default")
      (node (ref "IC1") (pin "7") (pinfunction "(MISO)PB6_7") (pintype "passive"))
      (node (ref "P1") (pin "5") (pinfunction "5_5") (pintype "passive"))
      (node (ref "R7") (pin "1") (pinfunction "1_1") (pintype "passive"))
    )
    (net (code "16") (name "/MM1") (class "Default")
      (node (ref "9") (pin "3") (pinfunction "G1_3") (pintype "passive"))
      (node (ref "9") (pin "8") (pinfunction "G2_8") (pintype "passive"))
      (node (ref "Q8") (pin "2") (pinfunction "E_2") (pintype "passive"))
    )
    (net (code "17") (name "/MM2") (class "Default")
      (node (ref "10") (pin "3") (pinfunction "G1_3") (pintype "passive"))
      (node (ref "10") (pin "8") (pinfunction "G2_8") (pintype "passive"))
      (node (ref "Q9") (pin "2") (pinfunction "E_2") (pintype "passive"))
    )
    (net (code "18") (name "/MOSI") (class "Default")
      (node (ref "IC1") (pin "6") (pinfunction "(MOSI)PB5_6") (pintype "passive"))
      (node (ref "P1") (pin "6") (pinfunction "6_6") (pintype "passive"))
      (node (ref "R11") (pin "1") (pinfunction "1_1") (pintype "passive"))
    )
    (net (code "20") (name "/P") (class "Default")
      (node (ref "1") (pin "5") (pinfunction "DP_5") (pintype "passive"))
      (node (ref "10") (pin "5") (pinfunction "DP_5") (pintype "passive"))
      (node (ref "11") (pin "5") (pinfunction "DP_5") (pintype "passive"))
      (node (ref "12") (pin "5") (pinfunction "DP_5") (pintype "passive"))
      (node (ref "13") (pin "5") (pinfunction "DP_5") (pintype "passive"))
      (node (ref "14") (pin "5") (pinfunction "DP_5") (pintype "passive"))
      (node (ref "2") (pin "5") (pinfunction "DP_5") (pintype "passive"))
      (node (ref "3") (pin "5") (pinfunction "DP_5") (pintype "passive"))
      (node (ref "4") (pin "5") (pinfunction "DP_5") (pintype "passive"))
      (node (ref "5") (pin "5") (pinfunction "DP_5") (pintype "passive"))
      (node (ref "6") (pin "5") (pinfunction "DP_5") (pintype "passive"))
      (node (ref "7") (pin "5") (pinfunction "DP_5") (pintype "passive"))
      (node (ref "8") (pin "5") (pinfunction "DP_5") (pintype "passive"))
      (node (ref "9") (pin "5") (pinfunction "DP_5") (pintype "passive"))
      (node (ref "R1") (pin "2") (pinfunction "2_2") (pintype "passive"))
    )
    (net (code "21") (name "/PC6") (class "Default")
      (node (ref "IC1") (pin "28") (pinfunction "(TOSC1)PC6_28") (pintype "passive"))
      (node (ref "R18") (pin "1") (pinfunction "1_1") (pintype "passive"))
    )
    (net (code "22") (name "/PC7") (class "Default")
      (node (ref "IC1") (pin "29") (pinfunction "(TOSC2)PC7_29") (pintype "passive"))
      (node (ref "R14") (pin "1") (pinfunction "1_1") (pintype "passive"))
    )
    (net (code "23") (name "/PD4") (class "Default")
      (node (ref "IC1") (pin "18") (pinfunction "(OC1B)PD4_18") (pintype "passive"))
      (node (ref "R24") (pin "1") (pinfunction "1_1") (pintype "passive"))
    )
    (net (code "24") (name "/PD5") (class "Default")
      (node (ref "IC1") (pin "19") (pinfunction "(OC1A)PD5_19") (pintype "passive"))
      (node (ref "R22") (pin "1") (pinfunction "1_1") (pintype "passive"))
    )
    (net (code "25") (name "/PD6") (class "Default")
      (node (ref "IC1") (pin "20") (pinfunction "(ICP)PD6_20") (pintype "passive"))
      (node (ref "R20") (pin "1") (pinfunction "1_1") (pintype "passive"))
    )
    (net (code "26") (name "/PD7") (class "Default")
      (node (ref "IC1") (pin "21") (pinfunction "(OC2)PD7_21") (pintype "passive"))
      (node (ref "R19") (pin "1") (pinfunction "1_1") (pintype "passive"))
    )
    (net (code "27") (name "/RST") (class "Default")
      (node (ref "IC1") (pin "9") (pinfunction "RESET_9") (pintype "passive"))
      (node (ref "P1") (pin "3") (pinfunction "3_3") (pintype "passive"))
    )
    (net (code "28") (name "/S1") (class "Default")
      (node (ref "5") (pin "3") (pinfunction "G1_3") (pintype "passive"))
      (node (ref "5") (pin "8") (pinfunction "G2_8") (pintype "passive"))
      (node (ref "Q2") (pin "2") (pinfunction "E_2") (pintype "passive"))
    )
    (net (code "29") (name "/S2") (class "Default")
      (node (ref "6") (pin "3") (pinfunction "G1_3") (pintype "passive"))
      (node (ref "6") (pin "8") (pinfunction "G2_8") (pintype "passive"))
      (node (ref "Q1") (pin "2") (pinfunction "E_2") (pintype "passive"))
    )
    (net (code "30") (name "/SCK") (class "Default")
      (node (ref "IC1") (pin "8") (pinfunction "(SCK)PB7_8") (pintype "passive"))
      (node (ref "P1") (pin "4") (pinfunction "4_4") (pintype "passive"))
      (node (ref "R10") (pin "1") (pinfunction "1_1") (pintype "passive"))
    )
    (net (code "31") (name "/SCL") (class "Default")
      (node (ref "IC1") (pin "22") (pinfunction "(SCL)PC0_22") (pintype "passive"))
      (node (ref "P2") (pin "4") (pinfunction "4_4") (pintype "passive"))
      (node (ref "P3") (pin "4") (pinfunction "4_4") (pintype "passive"))
      (node (ref "R27") (pin "2") (pinfunction "2_2") (pintype "passive"))
    )
    (net (code "32") (name "/SDA") (class "Default")
      (node (ref "IC1") (pin "23") (pinfunction "(SDA)PC1_23") (pintype "passive"))
      (node (ref "P2") (pin "3") (pinfunction "3_3") (pintype "passive"))
      (node (ref "P3") (pin "3") (pinfunction "3_3") (pintype "passive"))
      (node (ref "R28") (pin "2") (pinfunction "2_2") (pintype "passive"))
    )
    (net (code "33") (name "/TMP1") (class "Default")
      (node (ref "7") (pin "3") (pinfunction "G1_3") (pintype "passive"))
      (node (ref "7") (pin "8") (pinfunction "G2_8") (pintype "passive"))
      (node (ref "Q13") (pin "2") (pinfunction "E_2") (pintype "passive"))
    )
    (net (code "34") (name "/TMP2") (class "Default")
      (node (ref "8") (pin "3") (pinfunction "G1_3") (pintype "passive"))
      (node (ref "8") (pin "8") (pinfunction "G2_8") (pintype "passive"))
      (node (ref "Q14") (pin "2") (pinfunction "E_2") (pintype "passive"))
    )
    (net (code "35") (name "/YY1") (class "Default")
      (node (ref "11") (pin "3") (pinfunction "G1_3") (pintype "passive"))
      (node (ref "11") (pin "8") (pinfunction "G2_8") (pintype "passive"))
      (node (ref "Q11") (pin "2") (pinfunction "E_2") (pintype "passive"))
    )
    (net (code "36") (name "/YY2") (class "Default")
      (node (ref "12") (pin "3") (pinfunction "G1_3") (pintype "passive"))
      (node (ref "12") (pin "8") (pinfunction "G2_8") (pintype "passive"))
      (node (ref "Q12") (pin "2") (pinfunction "E_2") (pintype "passive"))
    )
    (net (code "37") (name "GND") (class "Default")
      (node (ref "C1") (pin "1") (pinfunction "1_1") (pintype "passive"))
      (node (ref "C2") (pin "1") (pinfunction "1_1") (pintype "passive"))
      (node (ref "IC1") (pin "11") (pinfunction "GND_11") (pintype "power_in"))
      (node (ref "IC1") (pin "31") (pinfunction "GND_31") (pintype "power_in"))
      (node (ref "J1") (pin "5") (pinfunction "5_5") (pintype "passive"))
      (node (ref "J1") (pin "S") (pinfunction "SHIELD_S") (pintype "passive"))
      (node (ref "P1") (pin "1") (pinfunction "1_1") (pintype "passive"))
      (node (ref "P2") (pin "1") (pinfunction "1_1") (pintype "passive"))
      (node (ref "P3") (pin "1") (pinfunction "1_1") (pintype "passive"))
      (node (ref "S1") (pin "3") (pinfunction "2_3") (pintype "passive"))
      (node (ref "S2") (pin "3") (pinfunction "2_3") (pintype "passive"))
      (node (ref "S3") (pin "3") (pinfunction "2_3") (pintype "passive"))
      (node (ref "S4") (pin "3") (pinfunction "2_3") (pintype "passive"))
      (node (ref "U1") (pin "2") (pinfunction "GND_2") (pintype "power_in"))
    )
    (net (code "38") (name "Net-(D1-PadA)") (class "Default")
      (node (ref "D1") (pin "A") (pinfunction "A_A") (pintype "passive"))
      (node (ref "J1") (pin "1") (pinfunction "1_1") (pintype "passive"))
    )
    (net (code "39") (name "Net-(D2-PadC)") (class "Default")
      (node (ref "D2") (pin "C") (pinfunction "C_C") (pintype "passive"))
      (node (ref "P1") (pin "2") (pinfunction "2_2") (pintype "passive"))
    )
    (net (code "40") (name "Net-(IC1-(ADC0)PA0)") (class "Default")
      (node (ref "IC1") (pin "40") (pinfunction "(ADC0)PA0_40") (pintype "passive"))
      (node (ref "R9") (pin "1") (pinfunction "1_1") (pintype "passive"))
    )
    (net (code "41") (name "Net-(IC1-(ADC1)PA1)") (class "Default")
      (node (ref "IC1") (pin "39") (pinfunction "(ADC1)PA1_39") (pintype "passive"))
      (node (ref "R8") (pin "1") (pinfunction "1_1") (pintype "passive"))
    )
    (net (code "42") (name "Net-(IC1-(ADC2)PA2)") (class "Default")
      (node (ref "IC1") (pin "38") (pinfunction "(ADC2)PA2_38") (pintype "passive"))
      (node (ref "R6") (pin "1") (pinfunction "1_1") (pintype "passive"))
    )
    (net (code "43") (name "Net-(IC1-(ADC3)PA3)") (class "Default")
      (node (ref "IC1") (pin "37") (pinfunction "(ADC3)PA3_37") (pintype "passive"))
      (node (ref "R5") (pin "1") (pinfunction "1_1") (pintype "passive"))
    )
    (net (code "44") (name "Net-(IC1-(ADC4)PA4)") (class "Default")
      (node (ref "IC1") (pin "36") (pinfunction "(ADC4)PA4_36") (pintype "passive"))
      (node (ref "R4") (pin "1") (pinfunction "1_1") (pintype "passive"))
    )
    (net (code "45") (name "Net-(IC1-(ADC5)PA5)") (class "Default")
      (node (ref "IC1") (pin "35") (pinfunction "(ADC5)PA5_35") (pintype "passive"))
      (node (ref "R3") (pin "1") (pinfunction "1_1") (pintype "passive"))
    )
    (net (code "46") (name "Net-(IC1-(ADC6)PA6)") (class "Default")
      (node (ref "IC1") (pin "34") (pinfunction "(ADC6)PA6_34") (pintype "passive"))
      (node (ref "R2") (pin "1") (pinfunction "1_1") (pintype "passive"))
    )
    (net (code "47") (name "Net-(IC1-(ADC7)PA7)") (class "Default")
      (node (ref "IC1") (pin "33") (pinfunction "(ADC7)PA7_33") (pintype "passive"))
      (node (ref "R1") (pin "1") (pinfunction "1_1") (pintype "passive"))
    )
    (net (code "48") (name "Net-(IC1-(AIN0{slash}INT2)PB2)") (class "Default")
      (node (ref "IC1") (pin "3") (pinfunction "(AIN0/INT2)PB2_3") (pintype "passive"))
      (node (ref "R15") (pin "1") (pinfunction "1_1") (pintype "passive"))
    )
    (net (code "49") (name "Net-(IC1-(AIN1{slash}OC0)PB3)") (class "Default")
      (node (ref "IC1") (pin "4") (pinfunction "(AIN1/OC0)PB3_4") (pintype "passive"))
      (node (ref "R13") (pin "1") (pinfunction "1_1") (pintype "passive"))
    )
    (net (code "50") (name "Net-(IC1-(SS)PB4)") (class "Default")
      (node (ref "IC1") (pin "5") (pinfunction "(SS)PB4_5") (pintype "passive"))
      (node (ref "R12") (pin "1") (pinfunction "1_1") (pintype "passive"))
    )
    (net (code "51") (name "Net-(IC1-(T0{slash}XCK)PB0)") (class "Default")
      (node (ref "IC1") (pin "1") (pinfunction "(T0/XCK)PB0_1") (pintype "passive"))
      (node (ref "R17") (pin "1") (pinfunction "1_1") (pintype "passive"))
    )
    (net (code "52") (name "Net-(IC1-(T1)PB1)") (class "Default")
      (node (ref "IC1") (pin "2") (pinfunction "(T1)PB1_2") (pintype "passive"))
      (node (ref "R16") (pin "1") (pinfunction "1_1") (pintype "passive"))
    )
    (net (code "53") (name "Net-(IC1-(TCK)PC2)") (class "Default")
      (node (ref "IC1") (pin "24") (pinfunction "(TCK)PC2_24") (pintype "passive"))
      (node (ref "R21") (pin "1") (pinfunction "1_1") (pintype "passive"))
      (node (ref "S1") (pin "1") (pinfunction "1_1") (pintype "passive"))
    )
    (net (code "54") (name "Net-(IC1-(TDI)PC5)") (class "Default")
      (node (ref "IC1") (pin "27") (pinfunction "(TDI)PC5_27") (pintype "passive"))
      (node (ref "R26") (pin "1") (pinfunction "1_1") (pintype "passive"))
      (node (ref "S4") (pin "1") (pinfunction "1_1") (pintype "passive"))
    )
    (net (code "55") (name "Net-(IC1-(TDO)PC4)") (class "Default")
      (node (ref "IC1") (pin "26") (pinfunction "(TDO)PC4_26") (pintype "passive"))
      (node (ref "R25") (pin "1") (pinfunction "1_1") (pintype "passive"))
      (node (ref "S3") (pin "1") (pinfunction "1_1") (pintype "passive"))
    )
    (net (code "56") (name "Net-(IC1-(TMS)PC3)") (class "Default")
      (node (ref "IC1") (pin "25") (pinfunction "(TMS)PC3_25") (pintype "passive"))
      (node (ref "R23") (pin "1") (pinfunction "1_1") (pintype "passive"))
      (node (ref "S2") (pin "1") (pinfunction "1_1") (pintype "passive"))
    )
    (net (code "57") (name "Net-(IC1-XTAL1)") (class "Default")
      (node (ref "C2") (pin "2") (pinfunction "2_2") (pintype "passive"))
      (node (ref "IC1") (pin "13") (pinfunction "XTAL1_13") (pintype "passive"))
      (node (ref "Y1") (pin "1") (pinfunction "1_1") (pintype "passive"))
    )
    (net (code "58") (name "Net-(IC1-XTAL2)") (class "Default")
      (node (ref "C1") (pin "2") (pinfunction "2_2") (pintype "passive"))
      (node (ref "IC1") (pin "12") (pinfunction "XTAL2_12") (pintype "passive"))
      (node (ref "Y1") (pin "2") (pinfunction "2_2") (pintype "passive"))
    )
    (net (code "59") (name "Net-(Q1-B)") (class "Default")
      (node (ref "Q1") (pin "1") (pinfunction "B_1") (pintype "passive"))
      (node (ref "R11") (pin "2") (pinfunction "2_2") (pintype "passive"))
    )
    (net (code "60") (name "Net-(Q2-B)") (class "Default")
      (node (ref "Q2") (pin "1") (pinfunction "B_1") (pintype "passive"))
      (node (ref "R12") (pin "2") (pinfunction "2_2") (pintype "passive"))
    )
    (net (code "61") (name "Net-(Q3-B)") (class "Default")
      (node (ref "Q3") (pin "1") (pinfunction "B_1") (pintype "passive"))
      (node (ref "R13") (pin "2") (pinfunction "2_2") (pintype "passive"))
    )
    (net (code "62") (name "Net-(Q4-B)") (class "Default")
      (node (ref "Q4") (pin "1") (pinfunction "B_1") (pintype "passive"))
      (node (ref "R7") (pin "2") (pinfunction "2_2") (pintype "passive"))
    )
    (net (code "63") (name "Net-(Q5-B)") (class "Default")
      (node (ref "Q5") (pin "1") (pinfunction "B_1") (pintype "passive"))
      (node (ref "R15") (pin "2") (pinfunction "2_2") (pintype "passive"))
    )
    (net (code "64") (name "Net-(Q6-B)") (class "Default")
      (node (ref "Q6") (pin "1") (pinfunction "B_1") (pintype "passive"))
      (node (ref "R10") (pin "2") (pinfunction "2_2") (pintype "passive"))
    )
    (net (code "65") (name "Net-(Q7-B)") (class "Default")
      (node (ref "Q7") (pin "1") (pinfunction "B_1") (pintype "passive"))
      (node (ref "R16") (pin "2") (pinfunction "2_2") (pintype "passive"))
    )
    (net (code "66") (name "Net-(Q8-B)") (class "Default")
      (node (ref "Q8") (pin "1") (pinfunction "B_1") (pintype "passive"))
      (node (ref "R14") (pin "2") (pinfunction "2_2") (pintype "passive"))
    )
    (net (code "67") (name "Net-(Q9-B)") (class "Default")
      (node (ref "Q9") (pin "1") (pinfunction "B_1") (pintype "passive"))
      (node (ref "R18") (pin "2") (pinfunction "2_2") (pintype "passive"))
    )
    (net (code "68") (name "Net-(Q10-B)") (class "Default")
      (node (ref "Q10") (pin "1") (pinfunction "B_1") (pintype "passive"))
      (node (ref "R17") (pin "2") (pinfunction "2_2") (pintype "passive"))
    )
    (net (code "69") (name "Net-(Q11-B)") (class "Default")
      (node (ref "Q11") (pin "1") (pinfunction "B_1") (pintype "passive"))
      (node (ref "R19") (pin "2") (pinfunction "2_2") (pintype "passive"))
    )
    (net (code "70") (name "Net-(Q12-B)") (class "Default")
      (node (ref "Q12") (pin "1") (pinfunction "B_1") (pintype "passive"))
      (node (ref "R20") (pin "2") (pinfunction "2_2") (pintype "passive"))
    )
    (net (code "71") (name "Net-(Q13-B)") (class "Default")
      (node (ref "Q13") (pin "1") (pinfunction "B_1") (pintype "passive"))
      (node (ref "R22") (pin "2") (pinfunction "2_2") (pintype "passive"))
    )
    (net (code "72") (name "Net-(Q14-B)") (class "Default")
      (node (ref "Q14") (pin "1") (pinfunction "B_1") (pintype "passive"))
      (node (ref "R24") (pin "2") (pinfunction "2_2") (pintype "passive"))
    )
    (net (code "73") (name "Net-(U1-IN)") (class "Default")
      (node (ref "D1") (pin "C") (pinfunction "C_C") (pintype "passive"))
      (node (ref "U1") (pin "1") (pinfunction "IN_1") (pintype "power_in"))
    )
    (net (code "74") (name "unconnected-(IC1-(INT0)PD2-Pad16)") (class "Default")
      (node (ref "IC1") (pin "16") (pinfunction "(INT0)PD2_16") (pintype "passive"))
    )
    (net (code "75") (name "unconnected-(IC1-(INT1)PD3-Pad17)") (class "Default")
      (node (ref "IC1") (pin "17") (pinfunction "(INT1)PD3_17") (pintype "passive"))
    )
    (net (code "76") (name "unconnected-(IC1-(RXD)PD0-Pad14)") (class "Default")
      (node (ref "IC1") (pin "14") (pinfunction "(RXD)PD0_14") (pintype "passive"))
    )
    (net (code "77") (name "unconnected-(IC1-(TXD)PD1-Pad15)") (class "Default")
      (node (ref "IC1") (pin "15") (pinfunction "(TXD)PD1_15") (pintype "passive"))
    )
    (net (code "78") (name "unconnected-(J1-Pad2)") (class "Default")
      (node (ref "J1") (pin "2") (pinfunction "2_2") (pintype "passive"))
    )
    (net (code "79") (name "unconnected-(J1-Pad3)") (class "Default")
      (node (ref "J1") (pin "3") (pinfunction "3_3") (pintype "passive"))
    )
    (net (code "80") (name "unconnected-(J1-Pad4)") (class "Default")
      (node (ref "J1") (pin "4") (pinfunction "4_4") (pintype "passive"))
    )
  )
)
